# CPU.net
KiCad netlist of a schematic drawn in Altium Designer
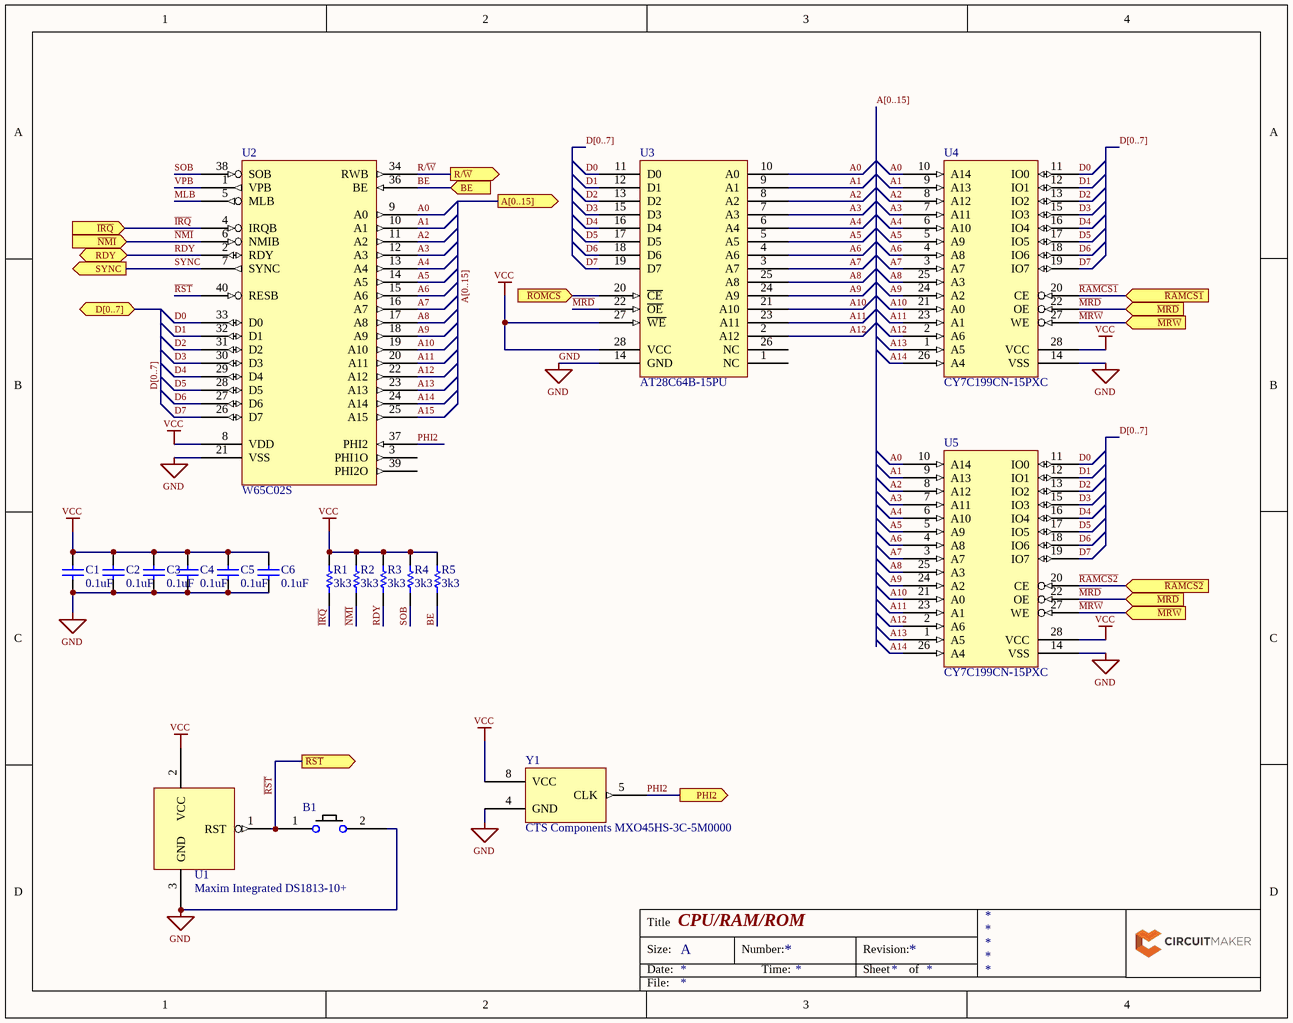
[diagram p0: CPU.SchDoc]

(export (version "E")
  (design (tool "Eeschema 10.0.6"))
  (components
    (comp (ref "B1")
      (value "TE Connectivity / AMP 2-1825910-7")
      (footprint "PCB-zc3gki7bdkzygyfrqq6y-1")
      (fields (field (name "MANUFACTURER PART NUMBER") "2-1825910-7"))
      (libsource (lib "CommunityVault") (part "SYM-3008f9696383efcf-1"))
    )
    (comp (ref "C1")
      (value "0.1uF")
      (footprint "CAPC1608X90X35NL15T15")
      (description "0603 0.1uF Capacitor")
      (libsource (lib "CommunityVault") (part "CAP-2"))
    )
    (comp (ref "C2")
      (value "0.1uF")
      (footprint "CAPC1608X90X35NL15T15")
      (description "0603 0.1uF Capacitor")
      (libsource (lib "CommunityVault") (part "CAP-2"))
    )
    (comp (ref "C3")
      (value "0.1uF")
      (footprint "CAPC1608X90X35NL15T15")
      (description "0603 0.1uF Capacitor")
      (libsource (lib "CommunityVault") (part "CAP-2"))
    )
    (comp (ref "C4")
      (value "0.1uF")
      (footprint "CAPC1608X90X35NL15T15")
      (description "0603 0.1uF Capacitor")
      (libsource (lib "CommunityVault") (part "CAP-2"))
    )
    (comp (ref "C5")
      (value "0.1uF")
      (footprint "CAPC1608X90X35NL15T15")
      (description "0603 0.1uF Capacitor")
      (libsource (lib "CommunityVault") (part "CAP-2"))
    )
    (comp (ref "C6")
      (value "0.1uF")
      (footprint "CAPC1608X90X35NL15T15")
      (description "0603 0.1uF Capacitor")
      (libsource (lib "CommunityVault") (part "CAP-2"))
    )
    (comp (ref "R1")
      (value "3k3")
      (footprint "RESC1608X55X30ML20T10")
      (description "Thick Film Resistors - SMD 1/10watt 3.3Kohms 1%")
      (libsource (lib "CommunityVault") (part "RES-2"))
    )
    (comp (ref "R2")
      (value "3k3")
      (footprint "RESC1608X55X30ML20T10")
      (description "Thick Film Resistors - SMD 1/10watt 3.3Kohms 1%")
      (libsource (lib "CommunityVault") (part "RES-2"))
    )
    (comp (ref "R3")
      (value "3k3")
      (footprint "RESC1608X55X30ML20T10")
      (description "Thick Film Resistors - SMD 1/10watt 3.3Kohms 1%")
      (libsource (lib "CommunityVault") (part "RES-2"))
    )
    (comp (ref "R4")
      (value "3k3")
      (footprint "RESC1608X55X30ML20T10")
      (description "Thick Film Resistors - SMD 1/10watt 3.3Kohms 1%")
      (libsource (lib "CommunityVault") (part "RES-2"))
    )
    (comp (ref "R5")
      (value "3k3")
      (footprint "RESC1608X55X30ML20T10")
      (description "Thick Film Resistors - SMD 1/10watt 3.3Kohms 1%")
      (libsource (lib "CommunityVault") (part "RES-2"))
    )
    (comp (ref "U1")
      (value "Maxim Integrated DS1813-10+")
      (footprint "PCB-n3dkw18s287l3ux4xt5g-1")
      (description "Processor Supervisor 4.35V 0V to 5.5V 3-Pin TO-92")
      (fields (field (name "MANUFACTURER PART NUMBER") "DS1813-10+"))
      (libsource (lib "CommunityVault") (part "SYM-1accd3d08fc8c50b-1"))
    )
    (comp (ref "U2")
      (value "W65C02S")
      (footprint "PCB-pok82zhzxzvu1tt0yxpn-1")
      (description "6502 CPU")
      (fields (field (name "MANUFACTURER PART NUMBER") "W65C02S6TPG-14"))
      (libsource (lib "CommunityVault") (part "CMP-6947a10c43c7b680-3"))
    )
    (comp (ref "U3")
      (value "AT28C64B-15PU")
      (footprint "PCB-0g11s820xjhkjlfxzqv3-1")
      (description "AT28C64B Series 64 KB (8 K x 8) 5.5 V High-Performance Parallel EEPROM - DIP-28")
      (libsource (lib "CommunityVault") (part "CMP-2d70e7372d9bf2b7-4"))
    )
    (comp (ref "U4")
      (value "CY7C199CN-15PXC")
      (footprint "PCB-dmo4zvmf3gxrfi0q9iqk-1")
      (description "SRAM Chip Async Single 5V 256K-bit 32K x 8 15ns 28-Pin PDIP Tube")
      (libsource (lib "CommunityVault") (part "CMP-7b4ab247c01fa48d-3"))
    )
    (comp (ref "U5")
      (value "CY7C199CN-15PXC")
      (footprint "PCB-dmo4zvmf3gxrfi0q9iqk-1")
      (description "SRAM Chip Async Single 5V 256K-bit 32K x 8 15ns 28-Pin PDIP Tube")
      (libsource (lib "CommunityVault") (part "CMP-7b4ab247c01fa48d-3"))
    )
    (comp (ref "Y1")
      (value "CTS Components MXO45HS-3C-5M0000")
      (footprint "PCBComponent_1 - duplicate")
      (description "Oscillator XO 5MHz ??50ppm 50pF (Stability) HCMOS/TTL 55% 5V 4-Pin Metal DIP Thru-Hole Tray")
      (fields (field (name "MANUFACTURER PART NUMBER") "MXO45HS-3C-5M0000"))
      (libsource (lib "CommunityVault") (part "SYM-6fd7a61dc048b010-1"))
    )
  )
  (nets
    (net (code "1") (name "/A0") (class "Default")
      (node (ref "U2") (pin "9") (pinfunction "A0_9") (pintype "output"))
      (node (ref "U3") (pin "10") (pinfunction "A0_10") (pintype "passive"))
      (node (ref "U4") (pin "10") (pinfunction "A14_10") (pintype "input"))
      (node (ref "U5") (pin "10") (pinfunction "A14_10") (pintype "input"))
    )
    (net (code "2") (name "/A1") (class "Default")
      (node (ref "U2") (pin "10") (pinfunction "A1_10") (pintype "output"))
      (node (ref "U3") (pin "9") (pinfunction "A1_9") (pintype "passive"))
      (node (ref "U4") (pin "9") (pinfunction "A13_9") (pintype "input"))
      (node (ref "U5") (pin "9") (pinfunction "A13_9") (pintype "input"))
    )
    (net (code "3") (name "/A2") (class "Default")
      (node (ref "U2") (pin "11") (pinfunction "A2_11") (pintype "output"))
      (node (ref "U3") (pin "8") (pinfunction "A2_8") (pintype "passive"))
      (node (ref "U4") (pin "8") (pinfunction "A12_8") (pintype "input"))
      (node (ref "U5") (pin "8") (pinfunction "A12_8") (pintype "input"))
    )
    (net (code "4") (name "/A3") (class "Default")
      (node (ref "U2") (pin "12") (pinfunction "A3_12") (pintype "output"))
      (node (ref "U3") (pin "7") (pinfunction "A3_7") (pintype "passive"))
      (node (ref "U4") (pin "7") (pinfunction "A11_7") (pintype "input"))
      (node (ref "U5") (pin "7") (pinfunction "A11_7") (pintype "input"))
    )
    (net (code "5") (name "/A4") (class "Default")
      (node (ref "U2") (pin "13") (pinfunction "A4_13") (pintype "output"))
      (node (ref "U3") (pin "6") (pinfunction "A4_6") (pintype "passive"))
      (node (ref "U4") (pin "6") (pinfunction "A10_6") (pintype "input"))
      (node (ref "U5") (pin "6") (pinfunction "A10_6") (pintype "input"))
    )
    (net (code "6") (name "/A5") (class "Default")
      (node (ref "U2") (pin "14") (pinfunction "A5_14") (pintype "output"))
      (node (ref "U3") (pin "5") (pinfunction "A5_5") (pintype "passive"))
      (node (ref "U4") (pin "5") (pinfunction "A9_5") (pintype "input"))
      (node (ref "U5") (pin "5") (pinfunction "A9_5") (pintype "input"))
    )
    (net (code "7") (name "/A6") (class "Default")
      (node (ref "U2") (pin "15") (pinfunction "A6_15") (pintype "output"))
      (node (ref "U3") (pin "4") (pinfunction "A6_4") (pintype "passive"))
      (node (ref "U4") (pin "4") (pinfunction "A8_4") (pintype "input"))
      (node (ref "U5") (pin "4") (pinfunction "A8_4") (pintype "input"))
    )
    (net (code "8") (name "/A7") (class "Default")
      (node (ref "U2") (pin "16") (pinfunction "A7_16") (pintype "output"))
      (node (ref "U3") (pin "3") (pinfunction "A7_3") (pintype "passive"))
      (node (ref "U4") (pin "3") (pinfunction "A7_3") (pintype "input"))
      (node (ref "U5") (pin "3") (pinfunction "A7_3") (pintype "input"))
    )
    (net (code "9") (name "/A8") (class "Default")
      (node (ref "U2") (pin "17") (pinfunction "A8_17") (pintype "output"))
      (node (ref "U3") (pin "25") (pinfunction "A8_25") (pintype "passive"))
      (node (ref "U4") (pin "25") (pinfunction "A3_25") (pintype "input"))
      (node (ref "U5") (pin "25") (pinfunction "A3_25") (pintype "input"))
    )
    (net (code "10") (name "/A9") (class "Default")
      (node (ref "U2") (pin "18") (pinfunction "A9_18") (pintype "output"))
      (node (ref "U3") (pin "24") (pinfunction "A9_24") (pintype "passive"))
      (node (ref "U4") (pin "24") (pinfunction "A2_24") (pintype "input"))
      (node (ref "U5") (pin "24") (pinfunction "A2_24") (pintype "input"))
    )
    (net (code "11") (name "/A10") (class "Default")
      (node (ref "U2") (pin "19") (pinfunction "A10_19") (pintype "output"))
      (node (ref "U3") (pin "21") (pinfunction "A10_21") (pintype "passive"))
      (node (ref "U4") (pin "21") (pinfunction "A0_21") (pintype "input"))
      (node (ref "U5") (pin "21") (pinfunction "A0_21") (pintype "input"))
    )
    (net (code "12") (name "/A11") (class "Default")
      (node (ref "U2") (pin "20") (pinfunction "A11_20") (pintype "output"))
      (node (ref "U3") (pin "23") (pinfunction "A11_23") (pintype "passive"))
      (node (ref "U4") (pin "23") (pinfunction "A1_23") (pintype "input"))
      (node (ref "U5") (pin "23") (pinfunction "A1_23") (pintype "input"))
    )
    (net (code "13") (name "/A12") (class "Default")
      (node (ref "U2") (pin "22") (pinfunction "A12_22") (pintype "output"))
      (node (ref "U3") (pin "2") (pinfunction "A12_2") (pintype "passive"))
      (node (ref "U4") (pin "2") (pinfunction "A6_2") (pintype "input"))
      (node (ref "U5") (pin "2") (pinfunction "A6_2") (pintype "input"))
    )
    (net (code "14") (name "/A13") (class "Default")
      (node (ref "U2") (pin "23") (pinfunction "A13_23") (pintype "output"))
      (node (ref "U4") (pin "1") (pinfunction "A5_1") (pintype "input"))
      (node (ref "U5") (pin "1") (pinfunction "A5_1") (pintype "input"))
    )
    (net (code "15") (name "/A14") (class "Default")
      (node (ref "U2") (pin "24") (pinfunction "A14_24") (pintype "output"))
      (node (ref "U4") (pin "26") (pinfunction "A4_26") (pintype "input"))
      (node (ref "U5") (pin "26") (pinfunction "A4_26") (pintype "input"))
    )
    (net (code "16") (name "/A15") (class "Default")
      (node (ref "U2") (pin "25") (pinfunction "A15_25") (pintype "output"))
    )
    (net (code "18") (name "/BE") (class "Default")
      (node (ref "R5") (pin "2") (pinfunction "2_2") (pintype "passive"))
      (node (ref "U2") (pin "36") (pinfunction "BE_36") (pintype "input"))
    )
    (net (code "19") (name "/D0") (class "Default")
      (node (ref "U2") (pin "33") (pinfunction "D0_33") (pintype "bidirectional"))
      (node (ref "U3") (pin "11") (pinfunction "D0_11") (pintype "passive"))
      (node (ref "U4") (pin "11") (pinfunction "IO0_11") (pintype "bidirectional"))
      (node (ref "U5") (pin "11") (pinfunction "IO0_11") (pintype "bidirectional"))
    )
    (net (code "20") (name "/D1") (class "Default")
      (node (ref "U2") (pin "32") (pinfunction "D1_32") (pintype "bidirectional"))
      (node (ref "U3") (pin "12") (pinfunction "D1_12") (pintype "passive"))
      (node (ref "U4") (pin "12") (pinfunction "IO1_12") (pintype "bidirectional"))
      (node (ref "U5") (pin "12") (pinfunction "IO1_12") (pintype "bidirectional"))
    )
    (net (code "21") (name "/D2") (class "Default")
      (node (ref "U2") (pin "31") (pinfunction "D2_31") (pintype "bidirectional"))
      (node (ref "U3") (pin "13") (pinfunction "D2_13") (pintype "passive"))
      (node (ref "U4") (pin "13") (pinfunction "IO2_13") (pintype "bidirectional"))
      (node (ref "U5") (pin "13") (pinfunction "IO2_13") (pintype "bidirectional"))
    )
    (net (code "22") (name "/D3") (class "Default")
      (node (ref "U2") (pin "30") (pinfunction "D3_30") (pintype "bidirectional"))
      (node (ref "U3") (pin "15") (pinfunction "D3_15") (pintype "passive"))
      (node (ref "U4") (pin "15") (pinfunction "IO3_15") (pintype "bidirectional"))
      (node (ref "U5") (pin "15") (pinfunction "IO3_15") (pintype "bidirectional"))
    )
    (net (code "23") (name "/D4") (class "Default")
      (node (ref "U2") (pin "29") (pinfunction "D4_29") (pintype "bidirectional"))
      (node (ref "U3") (pin "16") (pinfunction "D4_16") (pintype "passive"))
      (node (ref "U4") (pin "16") (pinfunction "IO4_16") (pintype "bidirectional"))
      (node (ref "U5") (pin "16") (pinfunction "IO4_16") (pintype "bidirectional"))
    )
    (net (code "24") (name "/D5") (class "Default")
      (node (ref "U2") (pin "28") (pinfunction "D5_28") (pintype "bidirectional"))
      (node (ref "U3") (pin "17") (pinfunction "D5_17") (pintype "passive"))
      (node (ref "U4") (pin "17") (pinfunction "IO5_17") (pintype "bidirectional"))
      (node (ref "U5") (pin "17") (pinfunction "IO5_17") (pintype "bidirectional"))
    )
    (net (code "25") (name "/D6") (class "Default")
      (node (ref "U2") (pin "27") (pinfunction "D6_27") (pintype "bidirectional"))
      (node (ref "U3") (pin "18") (pinfunction "D6_18") (pintype "passive"))
      (node (ref "U4") (pin "18") (pinfunction "IO6_18") (pintype "bidirectional"))
      (node (ref "U5") (pin "18") (pinfunction "IO6_18") (pintype "bidirectional"))
    )
    (net (code "26") (name "/D7") (class "Default")
      (node (ref "U2") (pin "26") (pinfunction "D7_26") (pintype "bidirectional"))
      (node (ref "U3") (pin "19") (pinfunction "D7_19") (pintype "passive"))
      (node (ref "U4") (pin "19") (pinfunction "IO7_19") (pintype "bidirectional"))
      (node (ref "U5") (pin "19") (pinfunction "IO7_19") (pintype "bidirectional"))
    )
    (net (code "28") (name "/MLB") (class "Default")
      (node (ref "U2") (pin "5") (pinfunction "MLB_5") (pintype "output"))
    )
    (net (code "29") (name "/PHI2") (class "Default")
      (node (ref "U2") (pin "37") (pinfunction "PHI2_37") (pintype "input"))
      (node (ref "Y1") (pin "5") (pinfunction "CLK_5") (pintype "output"))
    )
    (net (code "30") (name "/RDY") (class "Default")
      (node (ref "R3") (pin "2") (pinfunction "2_2") (pintype "passive"))
      (node (ref "U2") (pin "2") (pinfunction "RDY_2") (pintype "bidirectional"))
    )
    (net (code "31") (name "/R{slash}~{W}") (class "Default")
      (node (ref "U2") (pin "34") (pinfunction "RWB_34") (pintype "output"))
    )
    (net (code "32") (name "/SOB") (class "Default")
      (node (ref "R4") (pin "2") (pinfunction "2_2") (pintype "passive"))
      (node (ref "U2") (pin "38") (pinfunction "SOB_38") (pintype "input"))
    )
    (net (code "33") (name "/SYNC") (class "Default")
      (node (ref "U2") (pin "7") (pinfunction "SYNC_7") (pintype "output"))
    )
    (net (code "34") (name "/VPB") (class "Default")
      (node (ref "U2") (pin "1") (pinfunction "VPB_1") (pintype "output"))
    )
    (net (code "35") (name "/~{IRQ}") (class "Default")
      (node (ref "R1") (pin "2") (pinfunction "2_2") (pintype "passive"))
      (node (ref "U2") (pin "4") (pinfunction "IRQB_4") (pintype "input"))
    )
    (net (code "36") (name "/~{MRD}") (class "Default")
      (node (ref "U3") (pin "22") (pinfunction "~{OE}_22") (pintype "input"))
      (node (ref "U4") (pin "22") (pinfunction "OE_22") (pintype "input"))
      (node (ref "U5") (pin "22") (pinfunction "OE_22") (pintype "input"))
    )
    (net (code "37") (name "/~{MRW}") (class "Default")
      (node (ref "U4") (pin "27") (pinfunction "WE_27") (pintype "input"))
      (node (ref "U5") (pin "27") (pinfunction "WE_27") (pintype "input"))
    )
    (net (code "38") (name "/~{NMI}") (class "Default")
      (node (ref "R2") (pin "2") (pinfunction "2_2") (pintype "passive"))
      (node (ref "U2") (pin "6") (pinfunction "NMIB_6") (pintype "input"))
    )
    (net (code "39") (name "/~{RAMCS1}") (class "Default")
      (node (ref "U4") (pin "20") (pinfunction "CE_20") (pintype "input"))
    )
    (net (code "40") (name "/~{RAMCS2}") (class "Default")
      (node (ref "U5") (pin "20") (pinfunction "CE_20") (pintype "input"))
    )
    (net (code "41") (name "/~{ROMCS}") (class "Default")
      (node (ref "U3") (pin "20") (pinfunction "~{CE}_20") (pintype "input"))
    )
    (net (code "42") (name "/~{RST}") (class "Default")
      (node (ref "B1") (pin "1") (pinfunction "1_1") (pintype "passive"))
      (node (ref "U1") (pin "1") (pinfunction "RST_1") (pintype "output"))
      (node (ref "U2") (pin "40") (pinfunction "RESB_40") (pintype "input"))
    )
    (net (code "43") (name "GND") (class "Default")
      (node (ref "B1") (pin "2") (pinfunction "2_2") (pintype "passive"))
      (node (ref "C1") (pin "2") (pinfunction "2_2") (pintype "passive"))
      (node (ref "C2") (pin "2") (pinfunction "2_2") (pintype "passive"))
      (node (ref "C3") (pin "2") (pinfunction "2_2") (pintype "passive"))
      (node (ref "C4") (pin "2") (pinfunction "2_2") (pintype "passive"))
      (node (ref "C5") (pin "2") (pinfunction "2_2") (pintype "passive"))
      (node (ref "C6") (pin "2") (pinfunction "2_2") (pintype "passive"))
      (node (ref "U1") (pin "3") (pinfunction "GND_3") (pintype "power_in"))
      (node (ref "U2") (pin "21") (pinfunction "VSS_21") (pintype "power_in"))
      (node (ref "U3") (pin "14") (pinfunction "GND_14") (pintype "power_in"))
      (node (ref "U4") (pin "14") (pinfunction "VSS_14") (pintype "power_in"))
      (node (ref "U5") (pin "14") (pinfunction "VSS_14") (pintype "power_in"))
      (node (ref "Y1") (pin "4") (pinfunction "GND_4") (pintype "power_in"))
    )
    (net (code "44") (name "VCC") (class "Default")
      (node (ref "C1") (pin "1") (pinfunction "1_1") (pintype "passive"))
      (node (ref "C2") (pin "1") (pinfunction "1_1") (pintype "passive"))
      (node (ref "C3") (pin "1") (pinfunction "1_1") (pintype "passive"))
      (node (ref "C4") (pin "1") (pinfunction "1_1") (pintype "passive"))
      (node (ref "C5") (pin "1") (pinfunction "1_1") (pintype "passive"))
      (node (ref "C6") (pin "1") (pinfunction "1_1") (pintype "passive"))
      (node (ref "R1") (pin "1") (pinfunction "1_1") (pintype "passive"))
      (node (ref "R2") (pin "1") (pinfunction "1_1") (pintype "passive"))
      (node (ref "R3") (pin "1") (pinfunction "1_1") (pintype "passive"))
      (node (ref "R4") (pin "1") (pinfunction "1_1") (pintype "passive"))
      (node (ref "R5") (pin "1") (pinfunction "1_1") (pintype "passive"))
      (node (ref "U1") (pin "2") (pinfunction "VCC_2") (pintype "power_in"))
      (node (ref "U2") (pin "8") (pinfunction "VDD_8") (pintype "power_in"))
      (node (ref "U3") (pin "27") (pinfunction "~{WE}_27") (pintype "input"))
      (node (ref "U3") (pin "28") (pinfunction "VCC_28") (pintype "passive"))
      (node (ref "U4") (pin "28") (pinfunction "VCC_28") (pintype "power_in"))
      (node (ref "U5") (pin "28") (pinfunction "VCC_28") (pintype "power_in"))
      (node (ref "Y1") (pin "8") (pinfunction "VCC_8") (pintype "power_in"))
    )
    (net (code "45") (name "unconnected-(U2-PHI1O-Pad3)") (class "Default")
      (node (ref "U2") (pin "3") (pinfunction "PHI1O_3") (pintype "output"))
    )
    (net (code "46") (name "unconnected-(U2-PHI2O-Pad39)") (class "Default")
      (node (ref "U2") (pin "39") (pinfunction "PHI2O_39") (pintype "output"))
    )
    (net (code "47") (name "unconnected-(U3-NC-Pad1)") (class "Default")
      (node (ref "U3") (pin "1") (pinfunction "NC_1") (pintype "passive"))
    )
    (net (code "48") (name "unconnected-(U3-NC-Pad26)") (class "Default")
      (node (ref "U3") (pin "26") (pinfunction "NC_26") (pintype "passive"))
    )
    (net (code "49") (name "unconnected-(Y1-NC-Pad1)") (class "Default")
      (node (ref "Y1") (pin "1") (pinfunction "NC_1") (pintype "passive"))
    )
  )
)
